# Power_Board.net
KiCad netlist of a schematic drawn in EAGLE
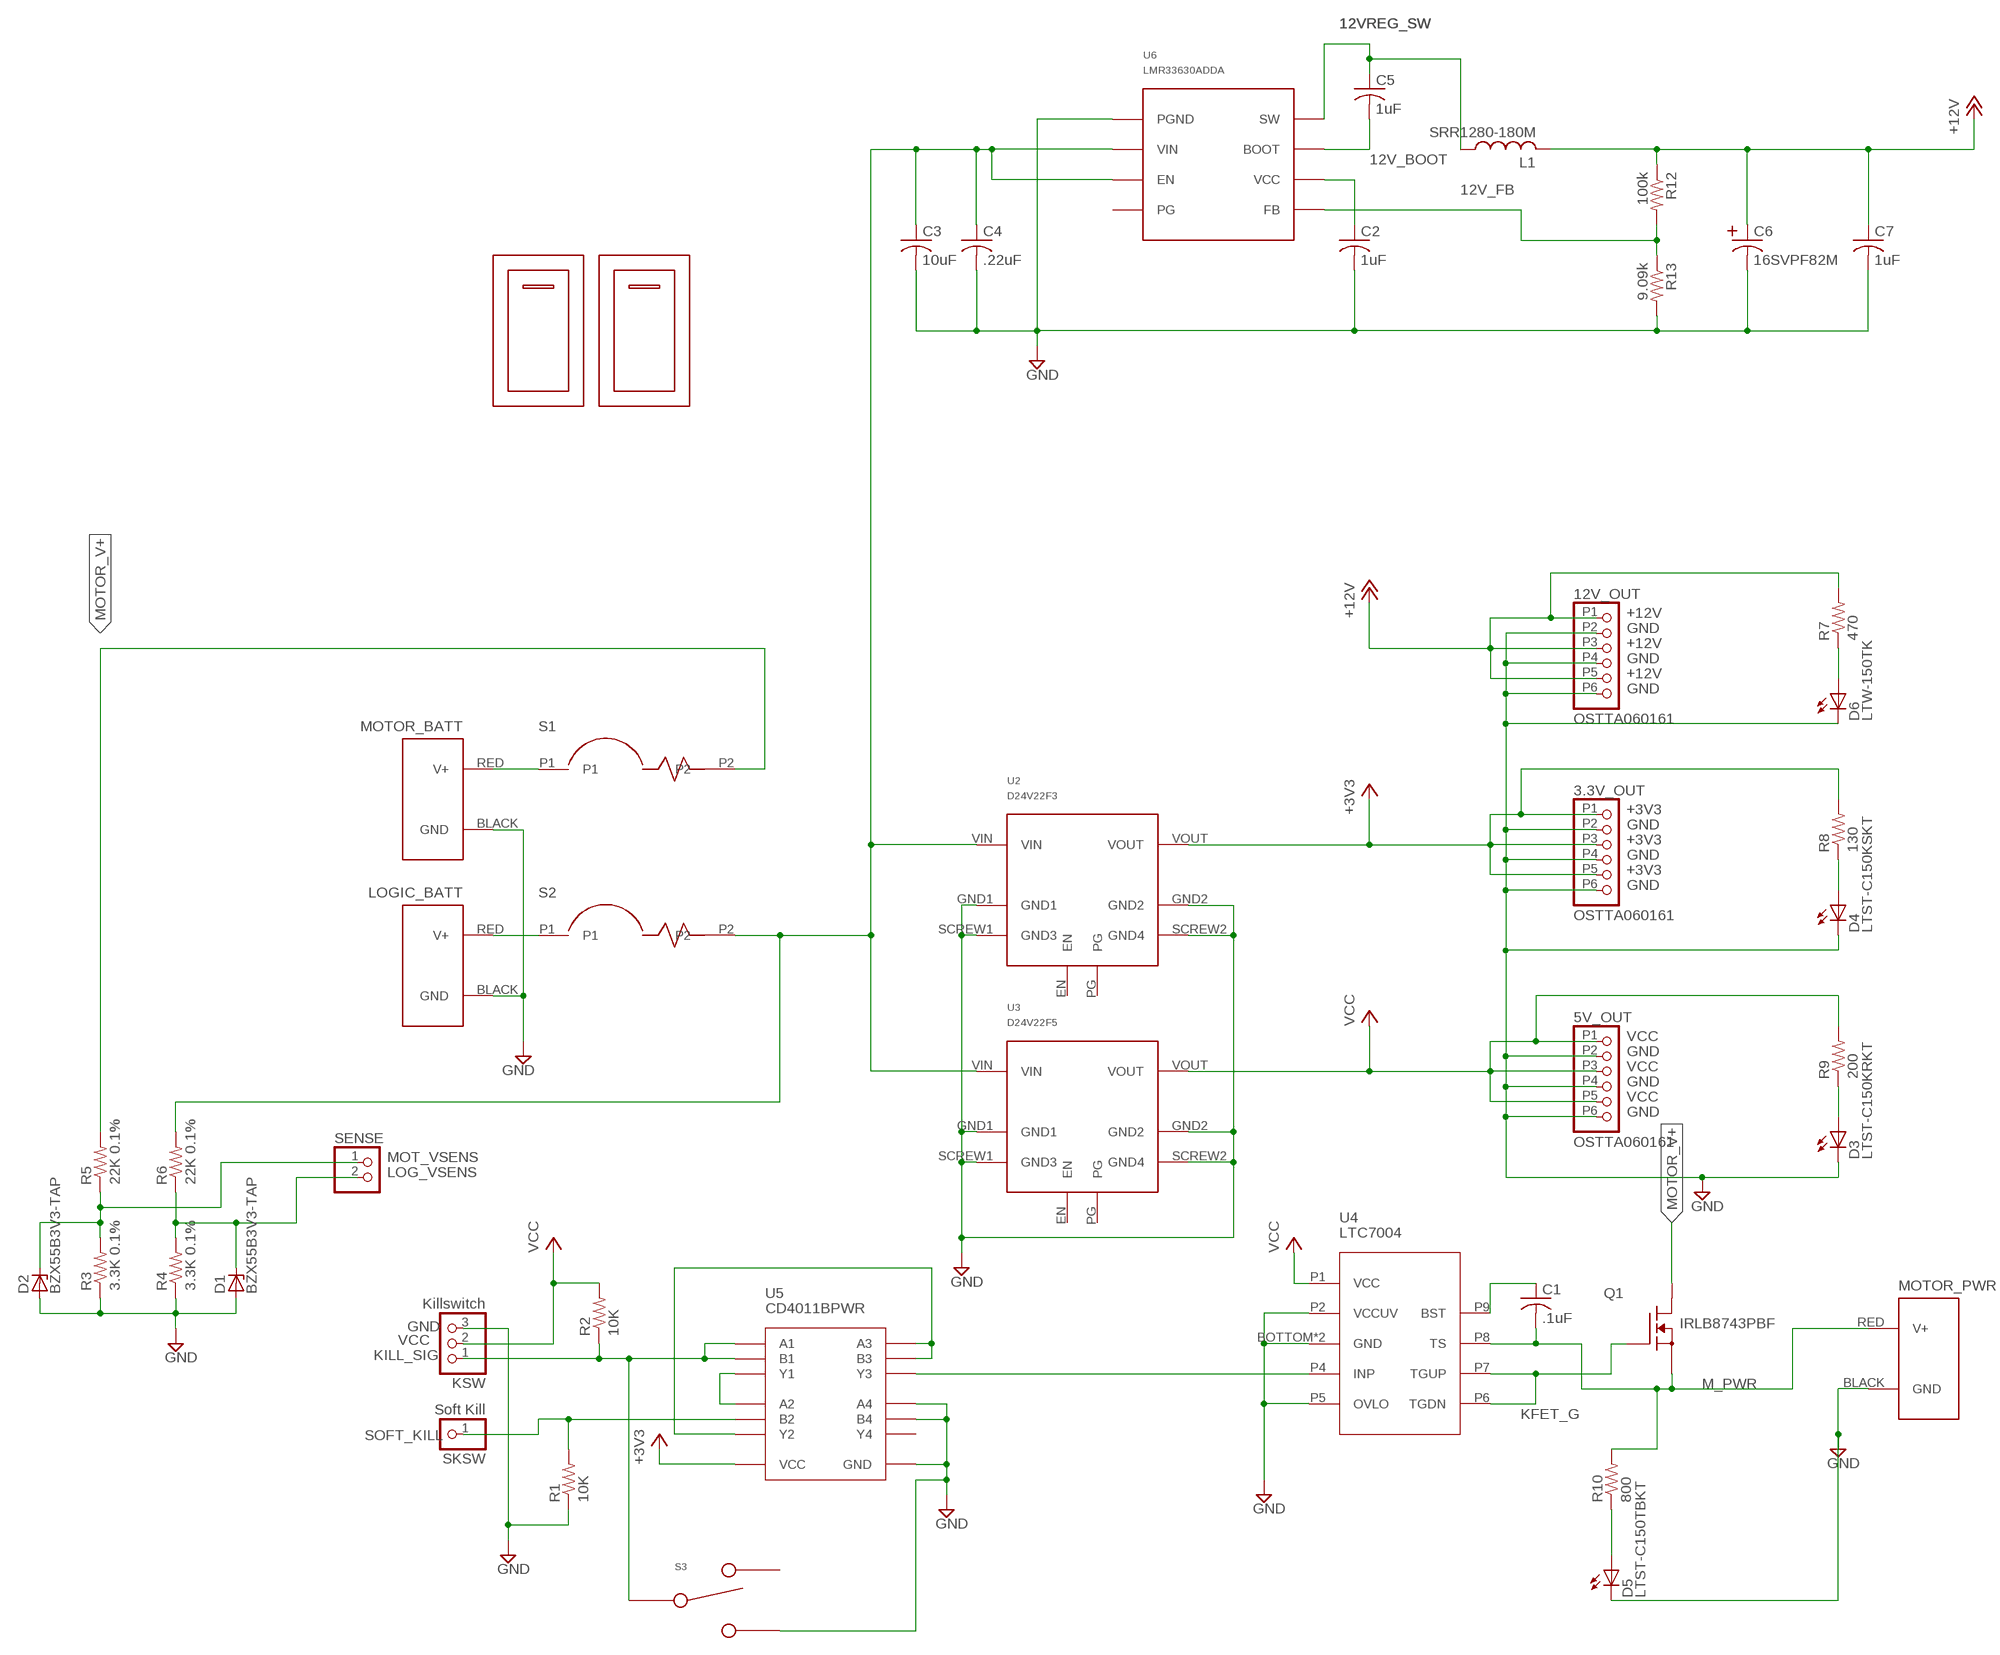
[diagram p0: schematic, sheet 1]

(export (version "E")
  (design (tool "Eeschema 10.0.6"))
  (components
    (comp (ref "3.3V_OUT")
      (value "OSTTA060161")
      (footprint "eagle-import:OSTTA06")
      (libsource (lib "eagle-import") (part "OSTTA060161"))
    )
    (comp (ref "5V_OUT")
      (value "OSTTA060161")
      (footprint "eagle-import:OSTTA06")
      (libsource (lib "eagle-import") (part "OSTTA060161"))
    )
    (comp (ref "12V_OUT")
      (value "OSTTA060161")
      (footprint "eagle-import:OSTTA06")
      (libsource (lib "eagle-import") (part "OSTTA060161"))
    )
    (comp (ref "C1")
      (value ".1uF")
      (footprint "eagle-import:C1206")
      (libsource (lib "eagle-import") (part "C-USC1206"))
    )
    (comp (ref "C2")
      (value "1uF")
      (footprint "eagle-import:C1206")
      (libsource (lib "eagle-import") (part "C-USC1206"))
    )
    (comp (ref "C3")
      (value "10uF")
      (footprint "eagle-import:C1206")
      (libsource (lib "eagle-import") (part "C-USC1206"))
    )
    (comp (ref "C4")
      (value ".22uF")
      (footprint "eagle-import:C1206")
      (libsource (lib "eagle-import") (part "C-USC1206"))
    )
    (comp (ref "C5")
      (value "1uF")
      (footprint "eagle-import:C1206")
      (libsource (lib "eagle-import") (part "C-USC1206"))
    )
    (comp (ref "C6")
      (value "16SVPF82M")
      (footprint "eagle-import:16SVPF82M")
      (libsource (lib "eagle-import") (part "16SVPF82M"))
    )
    (comp (ref "C7")
      (value "1uF")
      (footprint "eagle-import:C1206")
      (libsource (lib "eagle-import") (part "C-USC1206"))
    )
    (comp (ref "D1")
      (value "BZX55B3V3-TAP")
      (footprint "eagle-import:DO34Z7")
      (libsource (lib "eagle-import") (part "BZV10"))
    )
    (comp (ref "D2")
      (value "BZX55B3V3-TAP")
      (footprint "eagle-import:DO34Z7")
      (libsource (lib "eagle-import") (part "BZV10"))
    )
    (comp (ref "D3")
      (value "LTST-C150KRKT")
      (footprint "eagle-import:LITEON_LED_1206")
      (libsource (lib "eagle-import") (part "LTST-C150KRKT"))
    )
    (comp (ref "D4")
      (value "LTST-C150KSKT")
      (footprint "eagle-import:LITEON_LED_1206")
      (libsource (lib "eagle-import") (part "LTST-C150KSKT"))
    )
    (comp (ref "D5")
      (value "LTST-C150TBKT")
      (footprint "eagle-import:LITEON_LED_1206")
      (libsource (lib "eagle-import") (part "LTST-C150TBKT"))
    )
    (comp (ref "D6")
      (value "LTW-150TK")
      (footprint "eagle-import:LITEON_LED_1206")
      (libsource (lib "eagle-import") (part "LTW-150TK"))
    )
    (comp (ref "KSW")
      (value "Killswitch")
      (footprint "eagle-import:1X03")
      (libsource (lib "eagle-import") (part "PINHD-1X3"))
    )
    (comp (ref "L1")
      (value "SRR1280-180M")
      (footprint "eagle-import:SRR1280")
      (libsource (lib "eagle-import") (part "SRR1280-180M"))
    )
    (comp (ref "LOGIC_BATT")
      (value "POWERPOLE_POWER10AWG")
      (footprint "eagle-import:POWERPOLE_PAIR_10AWG")
      (libsource (lib "eagle-import") (part "POWERPOLE_POWER10AWG"))
    )
    (comp (ref "MOTOR_BATT")
      (value "POWERPOLE_POWER10AWG")
      (footprint "eagle-import:POWERPOLE_PAIR_10AWG")
      (libsource (lib "eagle-import") (part "POWERPOLE_POWER10AWG"))
    )
    (comp (ref "MOTOR_PWR")
      (value "POWERPOLE_POWER10AWG")
      (footprint "eagle-import:POWERPOLE_PAIR_10AWG")
      (libsource (lib "eagle-import") (part "POWERPOLE_POWER10AWG"))
    )
    (comp (ref "Q1")
      (value "IRLB8743PBF")
      (footprint "eagle-import:TO220")
      (libsource (lib "eagle-import") (part "IRLB8743PBF"))
    )
    (comp (ref "R1")
      (value "10K")
      (footprint "eagle-import:R1206")
      (libsource (lib "eagle-import") (part "R-US_R1206"))
    )
    (comp (ref "R2")
      (value "10K")
      (footprint "eagle-import:R1206")
      (libsource (lib "eagle-import") (part "R-US_R1206"))
    )
    (comp (ref "R3")
      (value "3.3K 0.1%")
      (footprint "eagle-import:R1206")
      (libsource (lib "eagle-import") (part "R-US_R1206"))
    )
    (comp (ref "R4")
      (value "3.3K 0.1%")
      (footprint "eagle-import:R1206")
      (libsource (lib "eagle-import") (part "R-US_R1206"))
    )
    (comp (ref "R5")
      (value "22K 0.1%")
      (footprint "eagle-import:R1206")
      (libsource (lib "eagle-import") (part "R-US_R1206"))
    )
    (comp (ref "R6")
      (value "22K 0.1%")
      (footprint "eagle-import:R1206")
      (libsource (lib "eagle-import") (part "R-US_R1206"))
    )
    (comp (ref "R7")
      (value "470")
      (footprint "eagle-import:R1206")
      (libsource (lib "eagle-import") (part "R-US_R1206"))
    )
    (comp (ref "R8")
      (value "130")
      (footprint "eagle-import:R1206")
      (libsource (lib "eagle-import") (part "R-US_R1206"))
    )
    (comp (ref "R9")
      (value "200")
      (footprint "eagle-import:R1206")
      (libsource (lib "eagle-import") (part "R-US_R1206"))
    )
    (comp (ref "R10")
      (value "800")
      (footprint "eagle-import:R1206")
      (libsource (lib "eagle-import") (part "R-US_R1206"))
    )
    (comp (ref "R12")
      (value "100k")
      (footprint "eagle-import:R1206")
      (libsource (lib "eagle-import") (part "R-US_R1206"))
    )
    (comp (ref "R13")
      (value "9.09k")
      (footprint "eagle-import:R1206")
      (libsource (lib "eagle-import") (part "R-US_R1206"))
    )
    (comp (ref "S1")
      (value "W51-A152A1-20")
      (footprint "eagle-import:W51-A152A1-PINS")
      (libsource (lib "eagle-import") (part "W51-A152A1-20"))
    )
    (comp (ref "S2")
      (value "W51-A152A1-20")
      (footprint "eagle-import:W51-A152A1-PINS")
      (libsource (lib "eagle-import") (part "W51-A152A1-20"))
    )
    (comp (ref "S3")
      (value "OS102011MS2QN1")
      (footprint "eagle-import:OS102011MS2Q")
      (libsource (lib "eagle-import") (part "OS102011MS2QN1"))
    )
    (comp (ref "SENSE")
      (value "PINHD-1X2")
      (footprint "eagle-import:1X02")
      (libsource (lib "eagle-import") (part "PINHD-1X2"))
    )
    (comp (ref "SKSW")
      (value "Soft Kill")
      (footprint "eagle-import:1X01")
      (libsource (lib "eagle-import") (part "PINHD-1X1"))
    )
    (comp (ref "U$1")
      (value "W51-A152A1-20-CUTOUT")
      (footprint "eagle-import:W51-A152A1-CUTOUT")
      (libsource (lib "eagle-import") (part "W51-A152A1-20-CUTOUT"))
    )
    (comp (ref "U$2")
      (value "W51-A152A1-20-CUTOUT")
      (footprint "eagle-import:W51-A152A1-CUTOUT")
      (libsource (lib "eagle-import") (part "W51-A152A1-20-CUTOUT"))
    )
    (comp (ref "U2")
      (value "D24V22F3")
      (footprint "eagle-import:D24V22")
      (libsource (lib "eagle-import") (part "D24V22F3"))
    )
    (comp (ref "U3")
      (value "D24V22F5")
      (footprint "eagle-import:D24V22")
      (libsource (lib "eagle-import") (part "D24V22F5"))
    )
    (comp (ref "U4")
      (value "LTC7004")
      (footprint "eagle-import:10-MSOP")
      (libsource (lib "eagle-import") (part "LTC7004"))
    )
    (comp (ref "U5")
      (value "CD4011BPWR")
      (footprint "eagle-import:14-TSSOP")
      (libsource (lib "eagle-import") (part "CD4011BPWR"))
    )
    (comp (ref "U6")
      (value "LMR33630ADDA")
      (footprint "eagle-import:HSOIC-8-POWERPAD")
      (libsource (lib "eagle-import") (part "LMR33630ADDA"))
    )
  )
  (nets
    (net (code "1") (name "+3V3") (class "Default")
      (node (ref "3.3V_OUT") (pin "P1") (pinfunction "1_P1") (pintype "passive"))
      (node (ref "3.3V_OUT") (pin "P3") (pinfunction "3_P3") (pintype "passive"))
      (node (ref "3.3V_OUT") (pin "P5") (pinfunction "5_P5") (pintype "passive"))
      (node (ref "R8") (pin "2") (pinfunction "2_2") (pintype "passive"))
      (node (ref "U2") (pin "VOUT") (pinfunction "VOUT_VOUT") (pintype "power_in"))
      (node (ref "U5") (pin "P14") (pinfunction "VCC_P14") (pintype "power_in"))
    )
    (net (code "2") (name "+12V") (class "Default")
      (node (ref "12V_OUT") (pin "P1") (pinfunction "1_P1") (pintype "passive"))
      (node (ref "12V_OUT") (pin "P3") (pinfunction "3_P3") (pintype "passive"))
      (node (ref "12V_OUT") (pin "P5") (pinfunction "5_P5") (pintype "passive"))
      (node (ref "C6") (pin "POS") (pinfunction "POS_POS") (pintype "passive"))
      (node (ref "C7") (pin "1") (pinfunction "1_1") (pintype "passive"))
      (node (ref "L1") (pin "2") (pinfunction "2_2") (pintype "passive"))
      (node (ref "R12") (pin "1") (pinfunction "1_1") (pintype "passive"))
      (node (ref "R7") (pin "2") (pinfunction "2_2") (pintype "passive"))
    )
    (net (code "3") (name "/12VREG_SW") (class "Default")
      (node (ref "C5") (pin "1") (pinfunction "1_1") (pintype "passive"))
      (node (ref "L1") (pin "1") (pinfunction "1_1") (pintype "passive"))
      (node (ref "U6") (pin "8") (pinfunction "SW_8") (pintype "bidirectional"))
    )
    (net (code "4") (name "/12V_BOOT") (class "Default")
      (node (ref "C5") (pin "2") (pinfunction "2_2") (pintype "passive"))
      (node (ref "U6") (pin "7") (pinfunction "BOOT_7") (pintype "bidirectional"))
    )
    (net (code "5") (name "/12V_FB") (class "Default")
      (node (ref "R12") (pin "2") (pinfunction "2_2") (pintype "passive"))
      (node (ref "R13") (pin "1") (pinfunction "1_1") (pintype "passive"))
      (node (ref "U6") (pin "5") (pinfunction "FB_5") (pintype "bidirectional"))
    )
    (net (code "6") (name "/KFET_G") (class "Default")
      (node (ref "Q1") (pin "G") (pinfunction "G_G") (pintype "passive"))
      (node (ref "U4") (pin "P6") (pinfunction "TGDN_P6") (pintype "bidirectional"))
      (node (ref "U4") (pin "P7") (pinfunction "TGUP_P7") (pintype "bidirectional"))
    )
    (net (code "7") (name "/KILL_SIG") (class "Default")
      (node (ref "KSW") (pin "1") (pinfunction "1_1") (pintype "passive"))
      (node (ref "R2") (pin "1") (pinfunction "1_1") (pintype "passive"))
      (node (ref "S3") (pin "C") (pinfunction "C_C") (pintype "bidirectional"))
      (node (ref "U5") (pin "P1") (pinfunction "A1_P1") (pintype "bidirectional"))
      (node (ref "U5") (pin "P2") (pinfunction "B1_P2") (pintype "bidirectional"))
    )
    (net (code "8") (name "/LOG_VSENS") (class "Default")
      (node (ref "D1") (pin "C") (pinfunction "C_C") (pintype "passive"))
      (node (ref "R4") (pin "2") (pinfunction "2_2") (pintype "passive"))
      (node (ref "R6") (pin "1") (pinfunction "1_1") (pintype "passive"))
      (node (ref "SENSE") (pin "2") (pinfunction "2_2") (pintype "passive"))
    )
    (net (code "9") (name "/MOT_VSENS") (class "Default")
      (node (ref "D2") (pin "C") (pinfunction "C_C") (pintype "passive"))
      (node (ref "R3") (pin "2") (pinfunction "2_2") (pintype "passive"))
      (node (ref "R5") (pin "1") (pinfunction "1_1") (pintype "passive"))
      (node (ref "SENSE") (pin "1") (pinfunction "1_1") (pintype "passive"))
    )
    (net (code "10") (name "/M_PWR") (class "Default")
      (node (ref "C1") (pin "2") (pinfunction "2_2") (pintype "passive"))
      (node (ref "MOTOR_PWR") (pin "RED") (pinfunction "V+_RED") (pintype "power_in"))
      (node (ref "Q1") (pin "S") (pinfunction "S_S") (pintype "passive"))
      (node (ref "R10") (pin "2") (pinfunction "2_2") (pintype "passive"))
      (node (ref "U4") (pin "P8") (pinfunction "TS_P8") (pintype "bidirectional"))
    )
    (net (code "11") (name "/SOFT_KILL") (class "Default")
      (node (ref "R1") (pin "2") (pinfunction "2_2") (pintype "passive"))
      (node (ref "SKSW") (pin "1") (pinfunction "1_1") (pintype "passive"))
      (node (ref "U5") (pin "P6") (pinfunction "B2_P6") (pintype "bidirectional"))
    )
    (net (code "12") (name "GND") (class "Default")
      (node (ref "12V_OUT") (pin "P2") (pinfunction "2_P2") (pintype "passive"))
      (node (ref "12V_OUT") (pin "P4") (pinfunction "4_P4") (pintype "passive"))
      (node (ref "12V_OUT") (pin "P6") (pinfunction "6_P6") (pintype "passive"))
      (node (ref "3.3V_OUT") (pin "P2") (pinfunction "2_P2") (pintype "passive"))
      (node (ref "3.3V_OUT") (pin "P4") (pinfunction "4_P4") (pintype "passive"))
      (node (ref "3.3V_OUT") (pin "P6") (pinfunction "6_P6") (pintype "passive"))
      (node (ref "5V_OUT") (pin "P2") (pinfunction "2_P2") (pintype "passive"))
      (node (ref "5V_OUT") (pin "P4") (pinfunction "4_P4") (pintype "passive"))
      (node (ref "5V_OUT") (pin "P6") (pinfunction "6_P6") (pintype "passive"))
      (node (ref "C2") (pin "2") (pinfunction "2_2") (pintype "passive"))
      (node (ref "C3") (pin "2") (pinfunction "2_2") (pintype "passive"))
      (node (ref "C4") (pin "2") (pinfunction "2_2") (pintype "passive"))
      (node (ref "C6") (pin "NEG") (pinfunction "NEG_NEG") (pintype "passive"))
      (node (ref "C7") (pin "2") (pinfunction "2_2") (pintype "passive"))
      (node (ref "D1") (pin "A") (pinfunction "A_A") (pintype "passive"))
      (node (ref "D2") (pin "A") (pinfunction "A_A") (pintype "passive"))
      (node (ref "D3") (pin "C") (pinfunction "C_C") (pintype "passive"))
      (node (ref "D4") (pin "C") (pinfunction "C_C") (pintype "passive"))
      (node (ref "D5") (pin "C") (pinfunction "C_C") (pintype "passive"))
      (node (ref "D6") (pin "C") (pinfunction "C_C") (pintype "passive"))
      (node (ref "KSW") (pin "3") (pinfunction "3_3") (pintype "passive"))
      (node (ref "LOGIC_BATT") (pin "BLACK") (pinfunction "GND_BLACK") (pintype "power_in"))
      (node (ref "MOTOR_BATT") (pin "BLACK") (pinfunction "GND_BLACK") (pintype "power_in"))
      (node (ref "MOTOR_PWR") (pin "BLACK") (pinfunction "GND_BLACK") (pintype "power_in"))
      (node (ref "R1") (pin "1") (pinfunction "1_1") (pintype "passive"))
      (node (ref "R13") (pin "2") (pinfunction "2_2") (pintype "passive"))
      (node (ref "R3") (pin "1") (pinfunction "1_1") (pintype "passive"))
      (node (ref "R4") (pin "1") (pinfunction "1_1") (pintype "passive"))
      (node (ref "S3") (pin "L") (pinfunction "L_L") (pintype "bidirectional"))
      (node (ref "U2") (pin "GND1") (pinfunction "GND1_GND1") (pintype "power_in"))
      (node (ref "U2") (pin "GND2") (pinfunction "GND2_GND2") (pintype "power_in"))
      (node (ref "U2") (pin "SCREW1") (pinfunction "GND3_SCREW1") (pintype "power_in"))
      (node (ref "U2") (pin "SCREW2") (pinfunction "GND4_SCREW2") (pintype "power_in"))
      (node (ref "U3") (pin "GND1") (pinfunction "GND1_GND1") (pintype "power_in"))
      (node (ref "U3") (pin "GND2") (pinfunction "GND2_GND2") (pintype "power_in"))
      (node (ref "U3") (pin "SCREW1") (pinfunction "GND3_SCREW1") (pintype "power_in"))
      (node (ref "U3") (pin "SCREW2") (pinfunction "GND4_SCREW2") (pintype "power_in"))
      (node (ref "U4") (pin "BOTTOM") (pinfunction "GND_BOTTOM") (pintype "power_in"))
      (node (ref "U4") (pin "P2") (pinfunction "VCCUV_P2") (pintype "bidirectional"))
      (node (ref "U4") (pin "P3") (pinfunction "GND_P3") (pintype "power_in"))
      (node (ref "U4") (pin "P5") (pinfunction "OVLO_P5") (pintype "bidirectional"))
      (node (ref "U5") (pin "P12") (pinfunction "A4_P12") (pintype "bidirectional"))
      (node (ref "U5") (pin "P13") (pinfunction "B4_P13") (pintype "bidirectional"))
      (node (ref "U5") (pin "P7") (pinfunction "GND_P7") (pintype "power_in"))
      (node (ref "U6") (pin "1") (pinfunction "PGND_1") (pintype "bidirectional"))
      (node (ref "U6") (pin "THERMAL") (pinfunction "PGND_THERMAL") (pintype "bidirectional"))
    )
    (net (code "13") (name "MOTOR_V+") (class "Default")
      (node (ref "Q1") (pin "D@1") (pinfunction "D_D@1") (pintype "passive"))
      (node (ref "Q1") (pin "D@2") (pinfunction "D_D@2") (pintype "passive"))
      (node (ref "R5") (pin "2") (pinfunction "2_2") (pintype "passive"))
      (node (ref "S1") (pin "P2") (pinfunction "P2_P2") (pintype "bidirectional"))
    )
    (net (code "14") (name "Net-(D3-PadA)") (class "Default")
      (node (ref "D3") (pin "A") (pinfunction "A_A") (pintype "passive"))
      (node (ref "R9") (pin "1") (pinfunction "1_1") (pintype "passive"))
    )
    (net (code "15") (name "Net-(D4-PadA)") (class "Default")
      (node (ref "D4") (pin "A") (pinfunction "A_A") (pintype "passive"))
      (node (ref "R8") (pin "1") (pinfunction "1_1") (pintype "passive"))
    )
    (net (code "16") (name "Net-(D5-PadA)") (class "Default")
      (node (ref "D5") (pin "A") (pinfunction "A_A") (pintype "passive"))
      (node (ref "R10") (pin "1") (pinfunction "1_1") (pintype "passive"))
    )
    (net (code "17") (name "Net-(D6-PadA)") (class "Default")
      (node (ref "D6") (pin "A") (pinfunction "A_A") (pintype "passive"))
      (node (ref "R7") (pin "1") (pinfunction "1_1") (pintype "passive"))
    )
    (net (code "18") (name "Net-(LOGIC_BATT-V+)") (class "Default")
      (node (ref "LOGIC_BATT") (pin "RED") (pinfunction "V+_RED") (pintype "power_in"))
      (node (ref "S2") (pin "P1") (pinfunction "P1_P1") (pintype "bidirectional"))
    )
    (net (code "19") (name "Net-(MOTOR_BATT-V+)") (class "Default")
      (node (ref "MOTOR_BATT") (pin "RED") (pinfunction "V+_RED") (pintype "power_in"))
      (node (ref "S1") (pin "P1") (pinfunction "P1_P1") (pintype "bidirectional"))
    )
    (net (code "20") (name "Net-(U4-BST)") (class "Default")
      (node (ref "C1") (pin "1") (pinfunction "1_1") (pintype "passive"))
      (node (ref "U4") (pin "P9") (pinfunction "BST_P9") (pintype "bidirectional"))
    )
    (net (code "21") (name "Net-(U4-INP)") (class "Default")
      (node (ref "U4") (pin "P4") (pinfunction "INP_P4") (pintype "bidirectional"))
      (node (ref "U5") (pin "P10") (pinfunction "Y3_P10") (pintype "bidirectional"))
    )
    (net (code "22") (name "Net-(U5-A2)") (class "Default")
      (node (ref "U5") (pin "P3") (pinfunction "Y1_P3") (pintype "bidirectional"))
      (node (ref "U5") (pin "P5") (pinfunction "A2_P5") (pintype "bidirectional"))
    )
    (net (code "23") (name "Net-(U5-A3)") (class "Default")
      (node (ref "U5") (pin "P4") (pinfunction "Y2_P4") (pintype "bidirectional"))
      (node (ref "U5") (pin "P8") (pinfunction "A3_P8") (pintype "bidirectional"))
      (node (ref "U5") (pin "P9") (pinfunction "B3_P9") (pintype "bidirectional"))
    )
    (net (code "24") (name "Net-(U6-EN)") (class "Default")
      (node (ref "C3") (pin "1") (pinfunction "1_1") (pintype "passive"))
      (node (ref "C4") (pin "1") (pinfunction "1_1") (pintype "passive"))
      (node (ref "R6") (pin "2") (pinfunction "2_2") (pintype "passive"))
      (node (ref "S2") (pin "P2") (pinfunction "P2_P2") (pintype "bidirectional"))
      (node (ref "U2") (pin "VIN") (pinfunction "VIN_VIN") (pintype "power_in"))
      (node (ref "U3") (pin "VIN") (pinfunction "VIN_VIN") (pintype "power_in"))
      (node (ref "U6") (pin "2") (pinfunction "VIN_2") (pintype "bidirectional"))
      (node (ref "U6") (pin "3") (pinfunction "EN_3") (pintype "bidirectional"))
    )
    (net (code "25") (name "Net-(U6-VCC)") (class "Default")
      (node (ref "C2") (pin "1") (pinfunction "1_1") (pintype "passive"))
      (node (ref "U6") (pin "6") (pinfunction "VCC_6") (pintype "bidirectional"))
    )
    (net (code "26") (name "VCC") (class "Default")
      (node (ref "5V_OUT") (pin "P1") (pinfunction "1_P1") (pintype "passive"))
      (node (ref "5V_OUT") (pin "P3") (pinfunction "3_P3") (pintype "passive"))
      (node (ref "5V_OUT") (pin "P5") (pinfunction "5_P5") (pintype "passive"))
      (node (ref "KSW") (pin "2") (pinfunction "2_2") (pintype "passive"))
      (node (ref "R2") (pin "2") (pinfunction "2_2") (pintype "passive"))
      (node (ref "R9") (pin "2") (pinfunction "2_2") (pintype "passive"))
      (node (ref "U3") (pin "VOUT") (pinfunction "VOUT_VOUT") (pintype "power_in"))
      (node (ref "U4") (pin "P1") (pinfunction "VCC_P1") (pintype "power_in"))
    )
    (net (code "27") (name "unconnected-(S3-PadR)") (class "Default")
      (node (ref "S3") (pin "R") (pinfunction "R_R") (pintype "bidirectional"))
    )
    (net (code "28") (name "unconnected-(U2-PadEN)") (class "Default")
      (node (ref "U2") (pin "EN") (pinfunction "EN_EN") (pintype "output"))
    )
    (net (code "29") (name "unconnected-(U2-PadPG)") (class "Default")
      (node (ref "U2") (pin "PG") (pinfunction "PG_PG") (pintype "input"))
    )
    (net (code "30") (name "unconnected-(U3-PadEN)") (class "Default")
      (node (ref "U3") (pin "EN") (pinfunction "EN_EN") (pintype "output"))
    )
    (net (code "31") (name "unconnected-(U3-PadPG)") (class "Default")
      (node (ref "U3") (pin "PG") (pinfunction "PG_PG") (pintype "input"))
    )
    (net (code "32") (name "unconnected-(U5-Y4-PadP11)") (class "Default")
      (node (ref "U5") (pin "P11") (pinfunction "Y4_P11") (pintype "bidirectional"))
    )
    (net (code "33") (name "unconnected-(U6-PG-Pad4)") (class "Default")
      (node (ref "U6") (pin "4") (pinfunction "PG_4") (pintype "bidirectional"))
    )
  )
)
